# midi_control.net
KiCad netlist of a schematic drawn in EAGLE
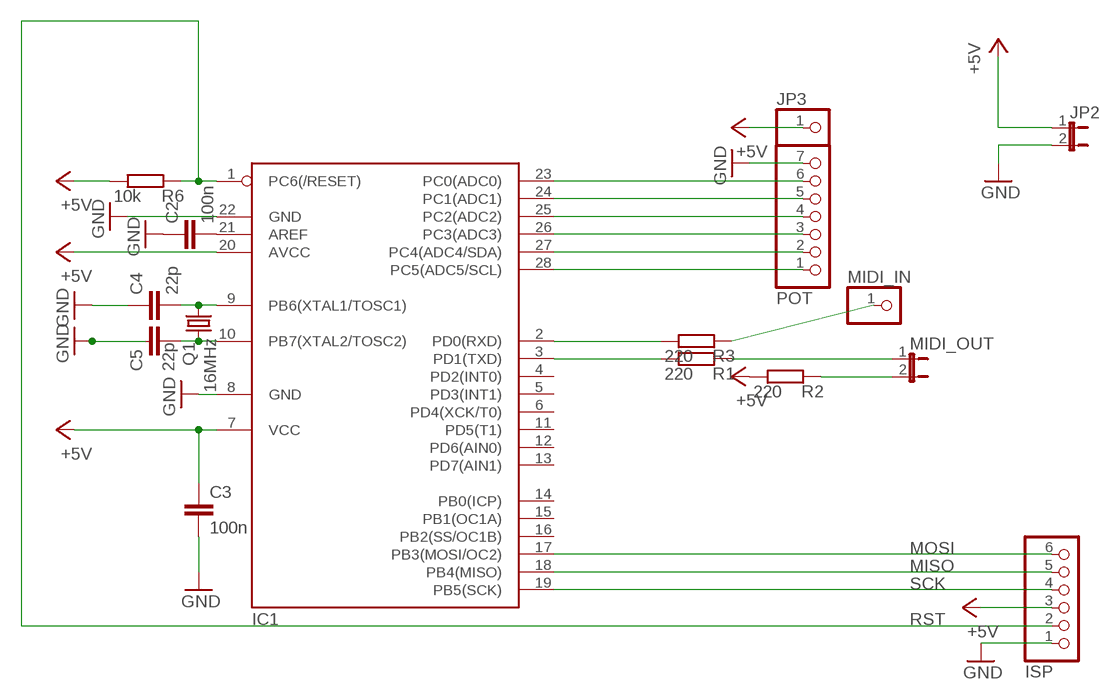
[diagram p0: schematic, sheet 1]

(export (version "E")
  (design (tool "Eeschema 10.0.6"))
  (components
    (comp (ref "C2")
      (value "100n")
      (footprint "eagle-import:C025-024X044")
      (libsource (lib "eagle-import") (part "C-EU025-024X044"))
    )
    (comp (ref "C3")
      (value "100n")
      (footprint "eagle-import:C025-024X044")
      (libsource (lib "eagle-import") (part "C-EU025-024X044"))
    )
    (comp (ref "C4")
      (value "22p")
      (footprint "eagle-import:C025-024X044")
      (libsource (lib "eagle-import") (part "C-EU025-024X044"))
    )
    (comp (ref "C5")
      (value "22p")
      (footprint "eagle-import:C050-025X075")
      (libsource (lib "eagle-import") (part "C-EU050-025X075"))
    )
    (comp (ref "IC1")
      (value "MEGA8-P")
      (footprint "eagle-import:DIL28-3")
      (libsource (lib "eagle-import") (part "MEGA8-P"))
    )
    (comp (ref "ISP")
      (value "PINHD-1X6/90")
      (footprint "eagle-import:1X06_90")
      (libsource (lib "eagle-import") (part "PINHD-1X6/90"))
    )
    (comp (ref "JP2")
      (value "JP1E")
      (footprint "eagle-import:JP1")
      (libsource (lib "eagle-import") (part "JP1E"))
    )
    (comp (ref "JP3")
      (value "PINHD-1X1")
      (footprint "eagle-import:1X01")
      (libsource (lib "eagle-import") (part "PINHD-1X1"))
    )
    (comp (ref "MIDI_IN")
      (value "PINHD-1X1")
      (footprint "eagle-import:1X01")
      (libsource (lib "eagle-import") (part "PINHD-1X1"))
    )
    (comp (ref "MIDI_OUT")
      (value "JP1E")
      (footprint "eagle-import:JP1")
      (libsource (lib "eagle-import") (part "JP1E"))
    )
    (comp (ref "POT")
      (value "PINHD-1X7")
      (footprint "eagle-import:1X07")
      (libsource (lib "eagle-import") (part "PINHD-1X7"))
    )
    (comp (ref "Q1")
      (value "16MHz")
      (footprint "eagle-import:TC26V")
      (libsource (lib "eagle-import") (part "CRYSTALTC26V"))
    )
    (comp (ref "R1")
      (value "220")
      (footprint "eagle-import:0207_10")
      (libsource (lib "eagle-import") (part "R-EU_0207/10"))
    )
    (comp (ref "R2")
      (value "220")
      (footprint "eagle-import:R0805")
      (libsource (lib "eagle-import") (part "R-EU_R0805"))
    )
    (comp (ref "R3")
      (value "220")
      (footprint "eagle-import:0207_10")
      (libsource (lib "eagle-import") (part "R-EU_0207/10"))
    )
    (comp (ref "R6")
      (value "10k")
      (footprint "eagle-import:0207_15")
      (libsource (lib "eagle-import") (part "R-EU_0207/15"))
    )
  )
  (nets
    (net (code "1") (name "+5V") (class "Default")
      (node (ref "C3") (pin "1") (pinfunction "1_1") (pintype "passive"))
      (node (ref "IC1") (pin "20") (pinfunction "AVCC_20") (pintype "power_in"))
      (node (ref "IC1") (pin "7") (pinfunction "VCC_7") (pintype "power_in"))
      (node (ref "ISP") (pin "3") (pinfunction "3_3") (pintype "passive"))
      (node (ref "JP2") (pin "1") (pinfunction "1_1") (pintype "passive"))
      (node (ref "JP3") (pin "1") (pinfunction "1_1") (pintype "passive"))
      (node (ref "R2") (pin "1") (pinfunction "1_1") (pintype "passive"))
      (node (ref "R6") (pin "1") (pinfunction "1_1") (pintype "passive"))
    )
    (net (code "2") (name "/MISO") (class "Default")
      (node (ref "IC1") (pin "18") (pinfunction "PB4(MISO)_18") (pintype "bidirectional"))
      (node (ref "ISP") (pin "5") (pinfunction "5_5") (pintype "passive"))
    )
    (net (code "3") (name "/MOSI") (class "Default")
      (node (ref "IC1") (pin "17") (pinfunction "PB3(MOSI/OC2)_17") (pintype "bidirectional"))
      (node (ref "ISP") (pin "6") (pinfunction "6_6") (pintype "passive"))
    )
    (net (code "4") (name "/RST") (class "Default")
      (node (ref "IC1") (pin "1") (pinfunction "PC6(/RESET)_1") (pintype "bidirectional"))
      (node (ref "ISP") (pin "2") (pinfunction "2_2") (pintype "passive"))
      (node (ref "R6") (pin "2") (pinfunction "2_2") (pintype "passive"))
    )
    (net (code "5") (name "/SCK") (class "Default")
      (node (ref "IC1") (pin "19") (pinfunction "PB5(SCK)_19") (pintype "bidirectional"))
      (node (ref "ISP") (pin "4") (pinfunction "4_4") (pintype "passive"))
    )
    (net (code "6") (name "GND") (class "Default")
      (node (ref "C2") (pin "1") (pinfunction "1_1") (pintype "passive"))
      (node (ref "C3") (pin "2") (pinfunction "2_2") (pintype "passive"))
      (node (ref "C4") (pin "1") (pinfunction "1_1") (pintype "passive"))
      (node (ref "C5") (pin "1") (pinfunction "1_1") (pintype "passive"))
      (node (ref "IC1") (pin "22") (pinfunction "GND_22") (pintype "power_in"))
      (node (ref "IC1") (pin "8") (pinfunction "GND_8") (pintype "power_in"))
      (node (ref "ISP") (pin "1") (pinfunction "1_1") (pintype "passive"))
      (node (ref "JP2") (pin "2") (pinfunction "2_2") (pintype "passive"))
      (node (ref "POT") (pin "7") (pinfunction "7_7") (pintype "passive"))
    )
    (net (code "7") (name "Net-(IC1-AREF)") (class "Default")
      (node (ref "C2") (pin "2") (pinfunction "2_2") (pintype "passive"))
      (node (ref "IC1") (pin "21") (pinfunction "AREF_21") (pintype "passive"))
    )
    (net (code "8") (name "Net-(IC1-PB6(XTAL1{slash}TOSC1))") (class "Default")
      (node (ref "C4") (pin "2") (pinfunction "2_2") (pintype "passive"))
      (node (ref "IC1") (pin "9") (pinfunction "PB6(XTAL1/TOSC1)_9") (pintype "bidirectional"))
      (node (ref "Q1") (pin "2") (pinfunction "2_2") (pintype "passive"))
    )
    (net (code "9") (name "Net-(IC1-PB7(XTAL2{slash}TOSC2))") (class "Default")
      (node (ref "C5") (pin "2") (pinfunction "2_2") (pintype "passive"))
      (node (ref "IC1") (pin "10") (pinfunction "PB7(XTAL2/TOSC2)_10") (pintype "bidirectional"))
      (node (ref "Q1") (pin "1") (pinfunction "1_1") (pintype "passive"))
    )
    (net (code "10") (name "Net-(IC1-PC0(ADC0))") (class "Default")
      (node (ref "IC1") (pin "23") (pinfunction "PC0(ADC0)_23") (pintype "bidirectional"))
      (node (ref "POT") (pin "6") (pinfunction "6_6") (pintype "passive"))
    )
    (net (code "11") (name "Net-(IC1-PC1(ADC1))") (class "Default")
      (node (ref "IC1") (pin "24") (pinfunction "PC1(ADC1)_24") (pintype "bidirectional"))
      (node (ref "POT") (pin "5") (pinfunction "5_5") (pintype "passive"))
    )
    (net (code "12") (name "Net-(IC1-PC2(ADC2))") (class "Default")
      (node (ref "IC1") (pin "25") (pinfunction "PC2(ADC2)_25") (pintype "bidirectional"))
      (node (ref "POT") (pin "4") (pinfunction "4_4") (pintype "passive"))
    )
    (net (code "13") (name "Net-(IC1-PC3(ADC3))") (class "Default")
      (node (ref "IC1") (pin "26") (pinfunction "PC3(ADC3)_26") (pintype "bidirectional"))
      (node (ref "POT") (pin "3") (pinfunction "3_3") (pintype "passive"))
    )
    (net (code "14") (name "Net-(IC1-PC4(ADC4{slash}SDA))") (class "Default")
      (node (ref "IC1") (pin "27") (pinfunction "PC4(ADC4/SDA)_27") (pintype "bidirectional"))
      (node (ref "POT") (pin "2") (pinfunction "2_2") (pintype "passive"))
    )
    (net (code "15") (name "Net-(IC1-PC5(ADC5{slash}SCL))") (class "Default")
      (node (ref "IC1") (pin "28") (pinfunction "PC5(ADC5/SCL)_28") (pintype "bidirectional"))
      (node (ref "POT") (pin "1") (pinfunction "1_1") (pintype "passive"))
    )
    (net (code "16") (name "Net-(IC1-PD0(RXD))") (class "Default")
      (node (ref "IC1") (pin "2") (pinfunction "PD0(RXD)_2") (pintype "bidirectional"))
      (node (ref "R3") (pin "1") (pinfunction "1_1") (pintype "passive"))
    )
    (net (code "17") (name "Net-(IC1-PD1(TXD))") (class "Default")
      (node (ref "IC1") (pin "3") (pinfunction "PD1(TXD)_3") (pintype "bidirectional"))
      (node (ref "R1") (pin "1") (pinfunction "1_1") (pintype "passive"))
    )
    (net (code "18") (name "Net-(MIDI_IN-Pad1)") (class "Default")
      (node (ref "MIDI_IN") (pin "1") (pinfunction "1_1") (pintype "passive"))
      (node (ref "R3") (pin "2") (pinfunction "2_2") (pintype "passive"))
    )
    (net (code "19") (name "Net-(MIDI_OUT-Pad1)") (class "Default")
      (node (ref "MIDI_OUT") (pin "1") (pinfunction "1_1") (pintype "passive"))
      (node (ref "R1") (pin "2") (pinfunction "2_2") (pintype "passive"))
    )
    (net (code "20") (name "Net-(MIDI_OUT-Pad2)") (class "Default")
      (node (ref "MIDI_OUT") (pin "2") (pinfunction "2_2") (pintype "passive"))
      (node (ref "R2") (pin "2") (pinfunction "2_2") (pintype "passive"))
    )
    (net (code "21") (name "unconnected-(IC1-PB0(ICP)-Pad14)") (class "Default")
      (node (ref "IC1") (pin "14") (pinfunction "PB0(ICP)_14") (pintype "bidirectional"))
    )
    (net (code "22") (name "unconnected-(IC1-PB1(OC1A)-Pad15)") (class "Default")
      (node (ref "IC1") (pin "15") (pinfunction "PB1(OC1A)_15") (pintype "bidirectional"))
    )
    (net (code "23") (name "unconnected-(IC1-PB2(SS{slash}OC1B)-Pad16)") (class "Default")
      (node (ref "IC1") (pin "16") (pinfunction "PB2(SS/OC1B)_16") (pintype "bidirectional"))
    )
    (net (code "24") (name "unconnected-(IC1-PD2(INT0)-Pad4)") (class "Default")
      (node (ref "IC1") (pin "4") (pinfunction "PD2(INT0)_4") (pintype "bidirectional"))
    )
    (net (code "25") (name "unconnected-(IC1-PD3(INT1)-Pad5)") (class "Default")
      (node (ref "IC1") (pin "5") (pinfunction "PD3(INT1)_5") (pintype "bidirectional"))
    )
    (net (code "26") (name "unconnected-(IC1-PD4(XCK{slash}T0)-Pad6)") (class "Default")
      (node (ref "IC1") (pin "6") (pinfunction "PD4(XCK/T0)_6") (pintype "bidirectional"))
    )
    (net (code "27") (name "unconnected-(IC1-PD5(T1)-Pad11)") (class "Default")
      (node (ref "IC1") (pin "11") (pinfunction "PD5(T1)_11") (pintype "bidirectional"))
    )
    (net (code "28") (name "unconnected-(IC1-PD6(AIN0)-Pad12)") (class "Default")
      (node (ref "IC1") (pin "12") (pinfunction "PD6(AIN0)_12") (pintype "bidirectional"))
    )
    (net (code "29") (name "unconnected-(IC1-PD7(AIN1)-Pad13)") (class "Default")
      (node (ref "IC1") (pin "13") (pinfunction "PD7(AIN1)_13") (pintype "bidirectional"))
    )
  )
)
